# JLinkV9-nano.net
KiCad netlist of a schematic drawn in Altium Designer
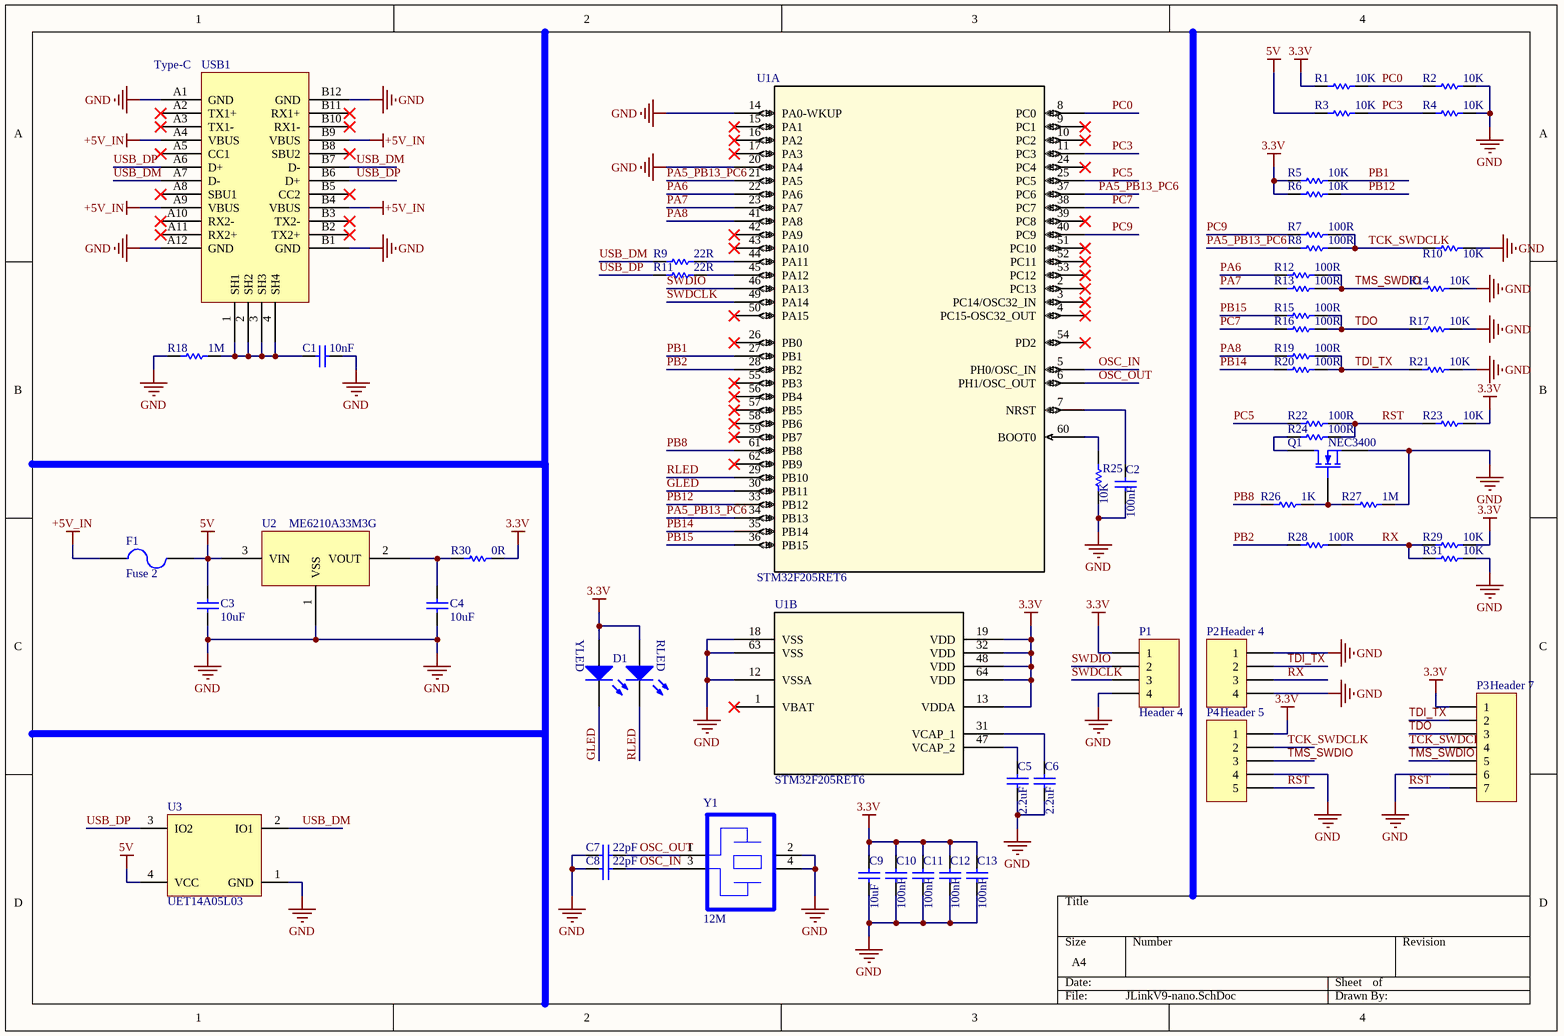
[diagram p0: JLinkV9-nano.SchDoc]

(export (version "E")
  (design (tool "Eeschema 10.0.6"))
  (components
    (comp (ref "C1")
      (value "10nF")
      (footprint "C0402")
      (description "Capacitor")
      (fields (field (name "Comment") "Cap") (field (name "PUBLISHER") "Altium Limited"))
      (libsource (lib "Misc") (part "Cap"))
    )
    (comp (ref "C2")
      (value "100nF")
      (footprint "C0402")
      (description "Capacitor")
      (fields (field (name "Comment") "Cap") (field (name "PUBLISHER") "Altium Limited"))
      (libsource (lib "Misc") (part "Cap"))
    )
    (comp (ref "C3")
      (value "10uF")
      (footprint "C0603")
      (description "Capacitor")
      (fields (field (name "Comment") "Cap") (field (name "PUBLISHER") "Altium Limited"))
      (libsource (lib "Misc") (part "Cap"))
    )
    (comp (ref "C4")
      (value "10uF")
      (footprint "C0603")
      (description "Capacitor")
      (fields (field (name "Comment") "Cap") (field (name "PUBLISHER") "Altium Limited"))
      (libsource (lib "Misc") (part "Cap"))
    )
    (comp (ref "C5")
      (value "2.2uF")
      (footprint "C0402")
      (description "Capacitor")
      (fields (field (name "Comment") "Cap") (field (name "PUBLISHER") "Altium Limited"))
      (libsource (lib "Misc") (part "Cap"))
    )
    (comp (ref "C6")
      (value "2.2uF")
      (footprint "C0402")
      (description "Capacitor")
      (fields (field (name "Comment") "Cap") (field (name "PUBLISHER") "Altium Limited"))
      (libsource (lib "Misc") (part "Cap"))
    )
    (comp (ref "C7")
      (value "22pF")
      (footprint "C0402")
      (description "Capacitor")
      (fields (field (name "Comment") "Cap") (field (name "PUBLISHER") "Altium Limited"))
      (libsource (lib "Misc") (part "Cap"))
    )
    (comp (ref "C8")
      (value "22pF")
      (footprint "C0402")
      (description "Capacitor")
      (fields (field (name "Comment") "Cap") (field (name "PUBLISHER") "Altium Limited"))
      (libsource (lib "Misc") (part "Cap"))
    )
    (comp (ref "C9")
      (value "10uF")
      (footprint "C0603")
      (description "Capacitor")
      (fields (field (name "Comment") "Cap") (field (name "PUBLISHER") "Altium Limited"))
      (libsource (lib "Misc") (part "Cap"))
    )
    (comp (ref "C10")
      (value "100nF")
      (footprint "C0402")
      (description "Capacitor")
      (fields (field (name "Comment") "Cap") (field (name "PUBLISHER") "Altium Limited"))
      (libsource (lib "Misc") (part "Cap"))
    )
    (comp (ref "C11")
      (value "100nF")
      (footprint "C0402")
      (description "Capacitor")
      (fields (field (name "Comment") "Cap") (field (name "PUBLISHER") "Altium Limited"))
      (libsource (lib "Misc") (part "Cap"))
    )
    (comp (ref "C12")
      (value "100nF")
      (footprint "C0402")
      (description "Capacitor")
      (fields (field (name "Comment") "Cap") (field (name "PUBLISHER") "Altium Limited"))
      (libsource (lib "Misc") (part "Cap"))
    )
    (comp (ref "C13")
      (value "100nF")
      (footprint "C0402")
      (description "Capacitor")
      (fields (field (name "Comment") "Cap") (field (name "PUBLISHER") "Altium Limited"))
      (libsource (lib "Misc") (part "Cap"))
    )
    (comp (ref "D1")
      (value "LED2")
      (footprint "LED_2")
      (description "Typical RED, GREEN, YELLOW, AMBER GaAs LED")
      (fields (field (name "PUBLISHER") "Altium Limited"))
      (libsource (lib "Misc") (part "LED2"))
    )
    (comp (ref "F1")
      (value "Fuse 2")
      (footprint "R0603")
      (description "Fuse")
      (fields (field (name "PUBLISHER") "Altium Limited"))
      (libsource (lib "Miscellaneous Devices") (part "Fuse 2"))
    )
    (comp (ref "P1")
      (value "Header 4")
      (footprint "2_0MM_4_HEADER")
      (description "Header, 4-Pin")
      (fields (field (name "PUBLISHER") "Altium Limited"))
      (libsource (lib "") (part "Header 4_1"))
    )
    (comp (ref "P2")
      (value "Header 4")
      (footprint "2_0MM_4_HEADER")
      (description "Header, 4-Pin")
      (fields (field (name "PUBLISHER") "Altium Limited"))
      (libsource (lib "Connector") (part "Header 4"))
    )
    (comp (ref "P3")
      (value "Header 7")
      (footprint "2_0MM_7_HEADER")
      (description "Header, 7-Pin")
      (fields (field (name "PUBLISHER") "Altium Limited"))
      (libsource (lib "Connector") (part "Header 7"))
    )
    (comp (ref "P4")
      (value "Header 5")
      (footprint "2_0MM_5_HEADER")
      (description "Header, 5-Pin")
      (fields (field (name "PUBLISHER") "Altium Limited"))
      (libsource (lib "Connector") (part "Header 5"))
    )
    (comp (ref "Q1")
      (value "NEC3400")
      (footprint "SOT-23_L")
      (description "N-Channel MOSFET")
      (fields (field (name "PUBLISHER") "Altium Limited"))
      (libsource (lib "Miscellaneous Devices") (part "MOSFET-N"))
    )
    (comp (ref "R1")
      (value "10K")
      (footprint "R0402")
      (description "Resistor")
      (fields (field (name "Comment") "Res") (field (name "PUBLISHER") "Altium Limited"))
      (libsource (lib "Misc") (part "Res"))
    )
    (comp (ref "R2")
      (value "10K")
      (footprint "R0402")
      (description "Resistor")
      (fields (field (name "Comment") "Res") (field (name "PUBLISHER") "Altium Limited"))
      (libsource (lib "Misc") (part "Res"))
    )
    (comp (ref "R3")
      (value "10K")
      (footprint "R0402")
      (description "Resistor")
      (fields (field (name "Comment") "Res") (field (name "PUBLISHER") "Altium Limited"))
      (libsource (lib "Misc") (part "Res"))
    )
    (comp (ref "R4")
      (value "10K")
      (footprint "R0402")
      (description "Resistor")
      (fields (field (name "Comment") "Res") (field (name "PUBLISHER") "Altium Limited"))
      (libsource (lib "Misc") (part "Res"))
    )
    (comp (ref "R5")
      (value "10K")
      (footprint "R0402")
      (description "Resistor")
      (fields (field (name "Comment") "Res") (field (name "PUBLISHER") "Altium Limited"))
      (libsource (lib "Misc") (part "Res"))
    )
    (comp (ref "R6")
      (value "10K")
      (footprint "R0402")
      (description "Resistor")
      (fields (field (name "Comment") "Res") (field (name "PUBLISHER") "Altium Limited"))
      (libsource (lib "Misc") (part "Res"))
    )
    (comp (ref "R7")
      (value "100R")
      (footprint "R0402")
      (description "Resistor")
      (fields (field (name "Comment") "Res") (field (name "PUBLISHER") "Altium Limited"))
      (libsource (lib "Misc") (part "Res"))
    )
    (comp (ref "R8")
      (value "100R")
      (footprint "R0402")
      (description "Resistor")
      (fields (field (name "Comment") "Res") (field (name "PUBLISHER") "Altium Limited"))
      (libsource (lib "Misc") (part "Res"))
    )
    (comp (ref "R9")
      (value "22R")
      (footprint "R0402")
      (description "Resistor")
      (fields (field (name "Comment") "Res") (field (name "PUBLISHER") "Altium Limited"))
      (libsource (lib "Misc") (part "Res"))
    )
    (comp (ref "R10")
      (value "10K")
      (footprint "R0402")
      (description "Resistor")
      (fields (field (name "Comment") "Res") (field (name "PUBLISHER") "Altium Limited"))
      (libsource (lib "Misc") (part "Res"))
    )
    (comp (ref "R11")
      (value "22R")
      (footprint "R0402")
      (description "Resistor")
      (fields (field (name "Comment") "Res") (field (name "PUBLISHER") "Altium Limited"))
      (libsource (lib "Misc") (part "Res"))
    )
    (comp (ref "R12")
      (value "100R")
      (footprint "R0402")
      (description "Resistor")
      (fields (field (name "Comment") "Res") (field (name "PUBLISHER") "Altium Limited"))
      (libsource (lib "Misc") (part "Res"))
    )
    (comp (ref "R13")
      (value "100R")
      (footprint "R0402")
      (description "Resistor")
      (fields (field (name "Comment") "Res") (field (name "PUBLISHER") "Altium Limited"))
      (libsource (lib "Misc") (part "Res"))
    )
    (comp (ref "R14")
      (value "10K")
      (footprint "R0402")
      (description "Resistor")
      (fields (field (name "Comment") "Res") (field (name "PUBLISHER") "Altium Limited"))
      (libsource (lib "Misc") (part "Res"))
    )
    (comp (ref "R15")
      (value "100R")
      (footprint "R0402")
      (description "Resistor")
      (fields (field (name "Comment") "Res") (field (name "PUBLISHER") "Altium Limited"))
      (libsource (lib "Misc") (part "Res"))
    )
    (comp (ref "R16")
      (value "100R")
      (footprint "R0402")
      (description "Resistor")
      (fields (field (name "Comment") "Res") (field (name "PUBLISHER") "Altium Limited"))
      (libsource (lib "Misc") (part "Res"))
    )
    (comp (ref "R17")
      (value "10K")
      (footprint "R0402")
      (description "Resistor")
      (fields (field (name "Comment") "Res") (field (name "PUBLISHER") "Altium Limited"))
      (libsource (lib "Misc") (part "Res"))
    )
    (comp (ref "R18")
      (value "1M")
      (footprint "R0402")
      (description "Resistor")
      (fields (field (name "Comment") "Res") (field (name "PUBLISHER") "Altium Limited"))
      (libsource (lib "Misc") (part "Res"))
    )
    (comp (ref "R19")
      (value "100R")
      (footprint "R0402")
      (description "Resistor")
      (fields (field (name "Comment") "Res") (field (name "PUBLISHER") "Altium Limited"))
      (libsource (lib "Misc") (part "Res"))
    )
    (comp (ref "R20")
      (value "100R")
      (footprint "R0402")
      (description "Resistor")
      (fields (field (name "Comment") "Res") (field (name "PUBLISHER") "Altium Limited"))
      (libsource (lib "Misc") (part "Res"))
    )
    (comp (ref "R21")
      (value "10K")
      (footprint "R0402")
      (description "Resistor")
      (fields (field (name "Comment") "Res") (field (name "PUBLISHER") "Altium Limited"))
      (libsource (lib "Misc") (part "Res"))
    )
    (comp (ref "R22")
      (value "100R")
      (footprint "R0402")
      (description "Resistor")
      (fields (field (name "Comment") "Res") (field (name "PUBLISHER") "Altium Limited"))
      (libsource (lib "Misc") (part "Res"))
    )
    (comp (ref "R23")
      (value "10K")
      (footprint "R0402")
      (description "Resistor")
      (fields (field (name "Comment") "Res") (field (name "PUBLISHER") "Altium Limited"))
      (libsource (lib "Misc") (part "Res"))
    )
    (comp (ref "R24")
      (value "100R")
      (footprint "R0402")
      (description "Resistor")
      (fields (field (name "Comment") "Res") (field (name "PUBLISHER") "Altium Limited"))
      (libsource (lib "Misc") (part "Res"))
    )
    (comp (ref "R25")
      (value "10K")
      (footprint "R0402")
      (description "Resistor")
      (fields (field (name "Comment") "Res") (field (name "PUBLISHER") "Altium Limited"))
      (libsource (lib "Misc") (part "Res"))
    )
    (comp (ref "R26")
      (value "1K")
      (footprint "R0402")
      (description "Resistor")
      (fields (field (name "Comment") "Res") (field (name "PUBLISHER") "Altium Limited"))
      (libsource (lib "Misc") (part "Res"))
    )
    (comp (ref "R27")
      (value "1M")
      (footprint "R0402")
      (description "Resistor")
      (fields (field (name "Comment") "Res") (field (name "PUBLISHER") "Altium Limited"))
      (libsource (lib "Misc") (part "Res"))
    )
    (comp (ref "R28")
      (value "100R")
      (footprint "R0402")
      (description "Resistor")
      (fields (field (name "Comment") "Res") (field (name "PUBLISHER") "Altium Limited"))
      (libsource (lib "Misc") (part "Res"))
    )
    (comp (ref "R29")
      (value "10K")
      (footprint "R0402")
      (description "Resistor")
      (fields (field (name "Comment") "Res") (field (name "PUBLISHER") "Altium Limited"))
      (libsource (lib "Misc") (part "Res"))
    )
    (comp (ref "R30")
      (value "0R")
      (footprint "R0402")
      (description "Resistor")
      (fields (field (name "Comment") "Res") (field (name "PUBLISHER") "Altium Limited"))
      (libsource (lib "Misc") (part "Res"))
    )
    (comp (ref "R31")
      (value "10K")
      (footprint "R0402")
      (description "Resistor")
      (fields (field (name "Comment") "Res") (field (name "PUBLISHER") "Altium Limited"))
      (libsource (lib "Misc") (part "Res"))
    )
    (comp (ref "U1")
      (value "STM32F205RET6")
      (footprint "LQFP64-10x10mm")
      (description "No Description Available")
      (fields (field (name "COPYRIGHT") "Copyright (C) 2021 Ultra Librarian. All rights reserved."))
      (libsource (lib "STM32F205RET6") (part "STM32F205RET6"))
    )
    (comp (ref "U2")
      (value "ME6210A33M3G")
      (footprint "SOT-23_L")
      (libsource (lib "ldo") (part "ME6210A33M3G"))
    )
    (comp (ref "U3") (value "UET14A05L03") (footprint "SOT-143_L") (libsource (lib "protect") (part "ESD4")))
    (comp (ref "USB1")
      (value "Type-C")
      (footprint "Connector:USB-Type-C")
      (libsource (lib "Connector") (part "USB-TYPE-C"))
    )
    (comp (ref "Y1") (value "12M") (footprint "XTAL4") (libsource (lib "Private") (part "XTAL4")))
  )
  (nets
    (net (code "1") (name "+5V_IN") (class "Default")
      (node (ref "F1") (pin "1") (pinfunction "1_1") (pintype "passive"))
      (node (ref "USB1") (pin "A4") (pinfunction "VBUS_A4") (pintype "passive"))
      (node (ref "USB1") (pin "A9") (pinfunction "VBUS_A9") (pintype "passive"))
      (node (ref "USB1") (pin "B4") (pinfunction "VBUS_B4") (pintype "passive"))
      (node (ref "USB1") (pin "B9") (pinfunction "VBUS_B9") (pintype "passive"))
    )
    (net (code "2") (name "/GLED") (class "Default")
      (node (ref "D1") (pin "4") (pinfunction "K_4") (pintype "passive"))
      (node (ref "U1") (pin "30") (pinfunction "PB11_30") (pintype "bidirectional"))
    )
    (net (code "3") (name "/OSC_IN") (class "Default")
      (node (ref "C8") (pin "1") (pinfunction "1_1") (pintype "passive"))
      (node (ref "U1") (pin "5") (pinfunction "PH0/OSC_IN_5") (pintype "bidirectional"))
      (node (ref "Y1") (pin "3") (pinfunction "OSC2_3") (pintype "passive"))
    )
    (net (code "4") (name "/OSC_OUT") (class "Default")
      (node (ref "C7") (pin "1") (pinfunction "1_1") (pintype "passive"))
      (node (ref "U1") (pin "6") (pinfunction "PH1/OSC_OUT_6") (pintype "bidirectional"))
      (node (ref "Y1") (pin "1") (pinfunction "OSC1_1") (pintype "passive"))
    )
    (net (code "5") (name "/PA5_PB13_PC6") (class "Default")
      (node (ref "R8") (pin "1") (pinfunction "1_1") (pintype "passive"))
      (node (ref "U1") (pin "21") (pinfunction "PA5_21") (pintype "bidirectional"))
      (node (ref "U1") (pin "34") (pinfunction "PB13_34") (pintype "bidirectional"))
      (node (ref "U1") (pin "37") (pinfunction "PC6_37") (pintype "bidirectional"))
    )
    (net (code "6") (name "/PA6") (class "Default")
      (node (ref "R12") (pin "1") (pinfunction "1_1") (pintype "passive"))
      (node (ref "U1") (pin "22") (pinfunction "PA6_22") (pintype "bidirectional"))
    )
    (net (code "7") (name "/PA7") (class "Default")
      (node (ref "R13") (pin "1") (pinfunction "1_1") (pintype "passive"))
      (node (ref "U1") (pin "23") (pinfunction "PA7_23") (pintype "bidirectional"))
    )
    (net (code "8") (name "/PA8") (class "Default")
      (node (ref "R19") (pin "1") (pinfunction "1_1") (pintype "passive"))
      (node (ref "U1") (pin "41") (pinfunction "PA8_41") (pintype "bidirectional"))
    )
    (net (code "9") (name "/PB1") (class "Default")
      (node (ref "R5") (pin "2") (pinfunction "2_2") (pintype "passive"))
      (node (ref "U1") (pin "27") (pinfunction "PB1_27") (pintype "bidirectional"))
    )
    (net (code "10") (name "/PB2") (class "Default")
      (node (ref "R28") (pin "1") (pinfunction "1_1") (pintype "passive"))
      (node (ref "U1") (pin "28") (pinfunction "PB2_28") (pintype "bidirectional"))
    )
    (net (code "11") (name "/PB8") (class "Default")
      (node (ref "R26") (pin "1") (pinfunction "1_1") (pintype "passive"))
      (node (ref "U1") (pin "61") (pinfunction "PB8_61") (pintype "bidirectional"))
    )
    (net (code "12") (name "/PB12") (class "Default")
      (node (ref "R6") (pin "2") (pinfunction "2_2") (pintype "passive"))
      (node (ref "U1") (pin "33") (pinfunction "PB12_33") (pintype "bidirectional"))
    )
    (net (code "13") (name "/PB14") (class "Default")
      (node (ref "R20") (pin "1") (pinfunction "1_1") (pintype "passive"))
      (node (ref "U1") (pin "35") (pinfunction "PB14_35") (pintype "bidirectional"))
    )
    (net (code "14") (name "/PB15") (class "Default")
      (node (ref "R15") (pin "1") (pinfunction "1_1") (pintype "passive"))
      (node (ref "U1") (pin "36") (pinfunction "PB15_36") (pintype "bidirectional"))
    )
    (net (code "15") (name "/PC0") (class "Default")
      (node (ref "R1") (pin "2") (pinfunction "2_2") (pintype "passive"))
      (node (ref "R2") (pin "1") (pinfunction "1_1") (pintype "passive"))
      (node (ref "U1") (pin "8") (pinfunction "PC0_8") (pintype "bidirectional"))
    )
    (net (code "16") (name "/PC3") (class "Default")
      (node (ref "R3") (pin "2") (pinfunction "2_2") (pintype "passive"))
      (node (ref "R4") (pin "1") (pinfunction "1_1") (pintype "passive"))
      (node (ref "U1") (pin "11") (pinfunction "PC3_11") (pintype "bidirectional"))
    )
    (net (code "17") (name "/PC5") (class "Default")
      (node (ref "R22") (pin "1") (pinfunction "1_1") (pintype "passive"))
      (node (ref "U1") (pin "25") (pinfunction "PC5_25") (pintype "bidirectional"))
    )
    (net (code "18") (name "/PC7") (class "Default")
      (node (ref "R16") (pin "1") (pinfunction "1_1") (pintype "passive"))
      (node (ref "U1") (pin "38") (pinfunction "PC7_38") (pintype "bidirectional"))
    )
    (net (code "19") (name "/PC9") (class "Default")
      (node (ref "R7") (pin "1") (pinfunction "1_1") (pintype "passive"))
      (node (ref "U1") (pin "40") (pinfunction "PC9_40") (pintype "bidirectional"))
    )
    (net (code "20") (name "/RLED") (class "Default")
      (node (ref "D1") (pin "2") (pinfunction "K_2") (pintype "passive"))
      (node (ref "U1") (pin "29") (pinfunction "PB10_29") (pintype "bidirectional"))
    )
    (net (code "21") (name "/RST") (class "Default")
      (node (ref "P3") (pin "7") (pinfunction "7_7") (pintype "passive"))
      (node (ref "P4") (pin "5") (pinfunction "5_5") (pintype "passive"))
      (node (ref "R22") (pin "2") (pinfunction "2_2") (pintype "passive"))
      (node (ref "R23") (pin "1") (pinfunction "1_1") (pintype "passive"))
      (node (ref "R24") (pin "2") (pinfunction "2_2") (pintype "passive"))
    )
    (net (code "22") (name "/RX") (class "Default")
      (node (ref "P2") (pin "3") (pinfunction "3_3") (pintype "passive"))
      (node (ref "R28") (pin "2") (pinfunction "2_2") (pintype "passive"))
      (node (ref "R29") (pin "1") (pinfunction "1_1") (pintype "passive"))
      (node (ref "R31") (pin "1") (pinfunction "1_1") (pintype "passive"))
    )
    (net (code "23") (name "/SWDCLK") (class "Default")
      (node (ref "P1") (pin "3") (pinfunction "3_3") (pintype "passive"))
      (node (ref "U1") (pin "49") (pinfunction "PA14_49") (pintype "bidirectional"))
    )
    (net (code "24") (name "/SWDIO") (class "Default")
      (node (ref "P1") (pin "2") (pinfunction "2_2") (pintype "passive"))
      (node (ref "U1") (pin "46") (pinfunction "PA13_46") (pintype "bidirectional"))
    )
    (net (code "25") (name "/TCK_SWDCLK") (class "Default")
      (node (ref "P3") (pin "4") (pinfunction "4_4") (pintype "passive"))
      (node (ref "P4") (pin "2") (pinfunction "2_2") (pintype "passive"))
      (node (ref "R10") (pin "1") (pinfunction "1_1") (pintype "passive"))
      (node (ref "R7") (pin "2") (pinfunction "2_2") (pintype "passive"))
      (node (ref "R8") (pin "2") (pinfunction "2_2") (pintype "passive"))
    )
    (net (code "26") (name "/TDI_TX") (class "Default")
      (node (ref "P2") (pin "2") (pinfunction "2_2") (pintype "passive"))
      (node (ref "P3") (pin "2") (pinfunction "2_2") (pintype "passive"))
      (node (ref "R19") (pin "2") (pinfunction "2_2") (pintype "passive"))
      (node (ref "R20") (pin "2") (pinfunction "2_2") (pintype "passive"))
      (node (ref "R21") (pin "1") (pinfunction "1_1") (pintype "passive"))
    )
    (net (code "27") (name "/TDO") (class "Default")
      (node (ref "P3") (pin "3") (pinfunction "3_3") (pintype "passive"))
      (node (ref "R15") (pin "2") (pinfunction "2_2") (pintype "passive"))
      (node (ref "R16") (pin "2") (pinfunction "2_2") (pintype "passive"))
      (node (ref "R17") (pin "1") (pinfunction "1_1") (pintype "passive"))
    )
    (net (code "28") (name "/TMS_SWDIO") (class "Default")
      (node (ref "P3") (pin "5") (pinfunction "5_5") (pintype "passive"))
      (node (ref "P4") (pin "3") (pinfunction "3_3") (pintype "passive"))
      (node (ref "R12") (pin "2") (pinfunction "2_2") (pintype "passive"))
      (node (ref "R13") (pin "2") (pinfunction "2_2") (pintype "passive"))
      (node (ref "R14") (pin "1") (pinfunction "1_1") (pintype "passive"))
    )
    (net (code "29") (name "/USB_DM") (class "Default")
      (node (ref "R9") (pin "1") (pinfunction "1_1") (pintype "passive"))
      (node (ref "U3") (pin "2") (pinfunction "IO1_2") (pintype "passive"))
      (node (ref "USB1") (pin "A7") (pinfunction "D-_A7") (pintype "passive"))
      (node (ref "USB1") (pin "B7") (pinfunction "D-_B7") (pintype "passive"))
    )
    (net (code "30") (name "/USB_DP") (class "Default")
      (node (ref "R11") (pin "1") (pinfunction "1_1") (pintype "passive"))
      (node (ref "U3") (pin "3") (pinfunction "IO2_3") (pintype "passive"))
      (node (ref "USB1") (pin "A6") (pinfunction "D+_A6") (pintype "passive"))
      (node (ref "USB1") (pin "B6") (pinfunction "D+_B6") (pintype "passive"))
    )
    (net (code "31") (name "3.3V") (class "Default")
      (node (ref "C10") (pin "2") (pinfunction "2_2") (pintype "passive"))
      (node (ref "C11") (pin "2") (pinfunction "2_2") (pintype "passive"))
      (node (ref "C12") (pin "2") (pinfunction "2_2") (pintype "passive"))
      (node (ref "C13") (pin "2") (pinfunction "2_2") (pintype "passive"))
      (node (ref "C9") (pin "2") (pinfunction "2_2") (pintype "passive"))
      (node (ref "D1") (pin "1") (pinfunction "A_1") (pintype "passive"))
      (node (ref "D1") (pin "3") (pinfunction "A_3") (pintype "passive"))
      (node (ref "P1") (pin "1") (pinfunction "1_1") (pintype "passive"))
      (node (ref "P3") (pin "1") (pinfunction "1_1") (pintype "passive"))
      (node (ref "P4") (pin "1") (pinfunction "1_1") (pintype "passive"))
      (node (ref "R1") (pin "1") (pinfunction "1_1") (pintype "passive"))
      (node (ref "R23") (pin "2") (pinfunction "2_2") (pintype "passive"))
      (node (ref "R29") (pin "2") (pinfunction "2_2") (pintype "passive"))
      (node (ref "R30") (pin "2") (pinfunction "2_2") (pintype "passive"))
      (node (ref "R5") (pin "1") (pinfunction "1_1") (pintype "passive"))
      (node (ref "R6") (pin "1") (pinfunction "1_1") (pintype "passive"))
      (node (ref "U1") (pin "13") (pinfunction "VDDA_13") (pintype "power_in"))
      (node (ref "U1") (pin "19") (pinfunction "VDD_19") (pintype "power_in"))
      (node (ref "U1") (pin "32") (pinfunction "VDD_32") (pintype "power_in"))
      (node (ref "U1") (pin "48") (pinfunction "VDD_48") (pintype "power_in"))
      (node (ref "U1") (pin "64") (pinfunction "VDD_64") (pintype "power_in"))
    )
    (net (code "32") (name "5V") (class "Default")
      (node (ref "C3") (pin "2") (pinfunction "2_2") (pintype "passive"))
      (node (ref "F1") (pin "2") (pinfunction "2_2") (pintype "passive"))
      (node (ref "R3") (pin "1") (pinfunction "1_1") (pintype "passive"))
      (node (ref "U2") (pin "3") (pinfunction "VIN_3") (pintype "passive"))
      (node (ref "U3") (pin "4") (pinfunction "VCC_4") (pintype "passive"))
    )
    (net (code "33") (name "GND") (class "Default")
      (node (ref "C1") (pin "2") (pinfunction "2_2") (pintype "passive"))
      (node (ref "C10") (pin "1") (pinfunction "1_1") (pintype "passive"))
      (node (ref "C11") (pin "1") (pinfunction "1_1") (pintype "passive"))
      (node (ref "C12") (pin "1") (pinfunction "1_1") (pintype "passive"))
      (node (ref "C13") (pin "1") (pinfunction "1_1") (pintype "passive"))
      (node (ref "C2") (pin "1") (pinfunction "1_1") (pintype "passive"))
      (node (ref "C3") (pin "1") (pinfunction "1_1") (pintype "passive"))
      (node (ref "C4") (pin "1") (pinfunction "1_1") (pintype "passive"))
      (node (ref "C5") (pin "1") (pinfunction "1_1") (pintype "passive"))
      (node (ref "C6") (pin "1") (pinfunction "1_1") (pintype "passive"))
      (node (ref "C7") (pin "2") (pinfunction "2_2") (pintype "passive"))
      (node (ref "C8") (pin "2") (pinfunction "2_2") (pintype "passive"))
      (node (ref "C9") (pin "1") (pinfunction "1_1") (pintype "passive"))
      (node (ref "P1") (pin "4") (pinfunction "4_4") (pintype "passive"))
      (node (ref "P2") (pin "1") (pinfunction "1_1") (pintype "passive"))
      (node (ref "P2") (pin "4") (pinfunction "4_4") (pintype "passive"))
      (node (ref "P3") (pin "6") (pinfunction "6_6") (pintype "passive"))
      (node (ref "P4") (pin "4") (pinfunction "4_4") (pintype "passive"))
      (node (ref "Q1") (pin "3") (pinfunction "S_3") (pintype "passive"))
      (node (ref "R10") (pin "2") (pinfunction "2_2") (pintype "passive"))
      (node (ref "R14") (pin "2") (pinfunction "2_2") (pintype "passive"))
      (node (ref "R17") (pin "2") (pinfunction "2_2") (pintype "passive"))
      (node (ref "R18") (pin "1") (pinfunction "1_1") (pintype "passive"))
      (node (ref "R2") (pin "2") (pinfunction "2_2") (pintype "passive"))
      (node (ref "R21") (pin "2") (pinfunction "2_2") (pintype "passive"))
      (node (ref "R25") (pin "1") (pinfunction "1_1") (pintype "passive"))
      (node (ref "R27") (pin "2") (pinfunction "2_2") (pintype "passive"))
      (node (ref "R31") (pin "2") (pinfunction "2_2") (pintype "passive"))
      (node (ref "R4") (pin "2") (pinfunction "2_2") (pintype "passive"))
      (node (ref "U1") (pin "12") (pinfunction "VSSA_12") (pintype "power_in"))
      (node (ref "U1") (pin "14") (pinfunction "PA0-WKUP_14") (pintype "bidirectional"))
      (node (ref "U1") (pin "18") (pinfunction "VSS_18") (pintype "power_in"))
      (node (ref "U1") (pin "20") (pinfunction "PA4_20") (pintype "bidirectional"))
      (node (ref "U1") (pin "63") (pinfunction "VSS_63") (pintype "power_in"))
      (node (ref "U2") (pin "1") (pinfunction "VSS_1") (pintype "passive"))
      (node (ref "U3") (pin "1") (pinfunction "GND_1") (pintype "passive"))
      (node (ref "USB1") (pin "A1") (pinfunction "GND_A1") (pintype "passive"))
      (node (ref "USB1") (pin "A12") (pinfunction "GND_A12") (pintype "passive"))
      (node (ref "USB1") (pin "B1") (pinfunction "GND_B1") (pintype "passive"))
      (node (ref "USB1") (pin "B12") (pinfunction "GND_B12") (pintype "passive"))
      (node (ref "Y1") (pin "2") (pinfunction "GND_2") (pintype "passive"))
      (node (ref "Y1") (pin "4") (pinfunction "GND_4") (pintype "passive"))
    )
    (net (code "34") (name "Net-(Q1-D)") (class "Default")
      (node (ref "Q1") (pin "1") (pinfunction "D_1") (pintype "passive"))
      (node (ref "R24") (pin "1") (pinfunction "1_1") (pintype "passive"))
    )
    (net (code "35") (name "Net-(Q1-G)") (class "Default")
      (node (ref "Q1") (pin "2") (pinfunction "G_2") (pintype "passive"))
      (node (ref "R26") (pin "2") (pinfunction "2_2") (pintype "passive"))
      (node (ref "R27") (pin "1") (pinfunction "1_1") (pintype "passive"))
    )
    (net (code "36") (name "Net-(U1A-BOOT0)") (class "Default")
      (node (ref "R25") (pin "2") (pinfunction "2_2") (pintype "passive"))
      (node (ref "U1") (pin "60") (pinfunction "BOOT0_60") (pintype "input"))
    )
    (net (code "37") (name "Net-(U1A-NRST)") (class "Default")
      (node (ref "C2") (pin "2") (pinfunction "2_2") (pintype "passive"))
      (node (ref "U1") (pin "7") (pinfunction "NRST_7") (pintype "bidirectional"))
    )
    (net (code "38") (name "Net-(U1A-PA11)") (class "Default")
      (node (ref "R9") (pin "2") (pinfunction "2_2") (pintype "passive"))
      (node (ref "U1") (pin "44") (pinfunction "PA11_44") (pintype "bidirectional"))
    )
    (net (code "39") (name "Net-(U1A-PA12)") (class "Default")
      (node (ref "R11") (pin "2") (pinfunction "2_2") (pintype "passive"))
      (node (ref "U1") (pin "45") (pinfunction "PA12_45") (pintype "bidirectional"))
    )
    (net (code "40") (name "Net-(U1B-VCAP_1)") (class "Default")
      (node (ref "C6") (pin "2") (pinfunction "2_2") (pintype "passive"))
      (node (ref "U1") (pin "31") (pinfunction "VCAP_1_31") (pintype "power_in"))
    )
    (net (code "41") (name "Net-(U1B-VCAP_2)") (class "Default")
      (node (ref "C5") (pin "2") (pinfunction "2_2") (pintype "passive"))
      (node (ref "U1") (pin "47") (pinfunction "VCAP_2_47") (pintype "power_in"))
    )
    (net (code "42") (name "Net-(U2-VOUT)") (class "Default")
      (node (ref "C4") (pin "2") (pinfunction "2_2") (pintype "passive"))
      (node (ref "R30") (pin "1") (pinfunction "1_1") (pintype "passive"))
      (node (ref "U2") (pin "2") (pinfunction "VOUT_2") (pintype "passive"))
    )
    (net (code "43") (name "Net-(USB1-SH1)") (class "Default")
      (node (ref "C1") (pin "1") (pinfunction "1_1") (pintype "passive"))
      (node (ref "R18") (pin "2") (pinfunction "2_2") (pintype "passive"))
      (node (ref "USB1") (pin "1") (pinfunction "SH1_1") (pintype "passive"))
      (node (ref "USB1") (pin "2") (pinfunction "SH2_2") (pintype "passive"))
      (node (ref "USB1") (pin "3") (pinfunction "SH3_3") (pintype "passive"))
      (node (ref "USB1") (pin "4") (pinfunction "SH4_4") (pintype "passive"))
    )
    (net (code "44") (name "unconnected-(U1A-PA1-Pad15)") (class "Default")
      (node (ref "U1") (pin "15") (pinfunction "PA1_15") (pintype "bidirectional+no_connect"))
    )
    (net (code "45") (name "unconnected-(U1A-PA2-Pad16)") (class "Default")
      (node (ref "U1") (pin "16") (pinfunction "PA2_16") (pintype "bidirectional+no_connect"))
    )
    (net (code "46") (name "unconnected-(U1A-PA3-Pad17)") (class "Default")
      (node (ref "U1") (pin "17") (pinfunction "PA3_17") (pintype "bidirectional+no_connect"))
    )
    (net (code "47") (name "unconnected-(U1A-PA9-Pad42)") (class "Default")
      (node (ref "U1") (pin "42") (pinfunction "PA9_42") (pintype "bidirectional+no_connect"))
    )
    (net (code "48") (name "unconnected-(U1A-PA10-Pad43)") (class "Default")
      (node (ref "U1") (pin "43") (pinfunction "PA10_43") (pintype "bidirectional+no_connect"))
    )
    (net (code "49") (name "unconnected-(U1A-PA15-Pad50)") (class "Default")
      (node (ref "U1") (pin "50") (pinfunction "PA15_50") (pintype "bidirectional+no_connect"))
    )
    (net (code "50") (name "unconnected-(U1A-PB0-Pad26)") (class "Default")
      (node (ref "U1") (pin "26") (pinfunction "PB0_26") (pintype "bidirectional+no_connect"))
    )
    (net (code "51") (name "unconnected-(U1A-PB3-Pad55)") (class "Default")
      (node (ref "U1") (pin "55") (pinfunction "PB3_55") (pintype "bidirectional+no_connect"))
    )
    (net (code "52") (name "unconnected-(U1A-PB4-Pad56)") (class "Default")
      (node (ref "U1") (pin "56") (pinfunction "PB4_56") (pintype "bidirectional+no_connect"))
    )
    (net (code "53") (name "unconnected-(U1A-PB5-Pad57)") (class "Default")
      (node (ref "U1") (pin "57") (pinfunction "PB5_57") (pintype "bidirectional+no_connect"))
    )
    (net (code "54") (name "unconnected-(U1A-PB6-Pad58)") (class "Default")
      (node (ref "U1") (pin "58") (pinfunction "PB6_58") (pintype "bidirectional+no_connect"))
    )
    (net (code "55") (name "unconnected-(U1A-PB7-Pad59)") (class "Default")
      (node (ref "U1") (pin "59") (pinfunction "PB7_59") (pintype "bidirectional+no_connect"))
    )
    (net (code "56") (name "unconnected-(U1A-PB9-Pad62)") (class "Default")
      (node (ref "U1") (pin "62") (pinfunction "PB9_62") (pintype "bidirectional+no_connect"))
    )
    (net (code "57") (name "unconnected-(U1A-PC1-Pad9)") (class "Default")
      (node (ref "U1") (pin "9") (pinfunction "PC1_9") (pintype "bidirectional+no_connect"))
    )
    (net (code "58") (name "unconnected-(U1A-PC2-Pad10)") (class "Default")
      (node (ref "U1") (pin "10") (pinfunction "PC2_10") (pintype "bidirectional+no_connect"))
    )
    (net (code "59") (name "unconnected-(U1A-PC4-Pad24)") (class "Default")
      (node (ref "U1") (pin "24") (pinfunction "PC4_24") (pintype "bidirectional+no_connect"))
    )
    (net (code "60") (name "unconnected-(U1A-PC8-Pad39)") (class "Default")
      (node (ref "U1") (pin "39") (pinfunction "PC8_39") (pintype "bidirectional+no_connect"))
    )
    (net (code "61") (name "unconnected-(U1A-PC10-Pad51)") (class "Default")
      (node (ref "U1") (pin "51") (pinfunction "PC10_51") (pintype "bidirectional+no_connect"))
    )
    (net (code "62") (name "unconnected-(U1A-PC11-Pad52)") (class "Default")
      (node (ref "U1") (pin "52") (pinfunction "PC11_52") (pintype "bidirectional+no_connect"))
    )
    (net (code "63") (name "unconnected-(U1A-PC12-Pad53)") (class "Default")
      (node (ref "U1") (pin "53") (pinfunction "PC12_53") (pintype "bidirectional+no_connect"))
    )
    (net (code "64") (name "unconnected-(U1A-PC13-Pad2)") (class "Default")
      (node (ref "U1") (pin "2") (pinfunction "PC13_2") (pintype "bidirectional+no_connect"))
    )
    (net (code "65") (name "unconnected-(U1A-PC14{slash}OSC32_IN-Pad3)") (class "Default")
      (node (ref "U1") (pin "3") (pinfunction "PC14/OSC32_IN_3") (pintype "bidirectional+no_connect"))
    )
    (net (code "66") (name "unconnected-(U1A-PC15-OSC32_OUT-Pad4)") (class "Default")
      (node (ref "U1") (pin "4") (pinfunction "PC15-OSC32_OUT_4") (pintype "bidirectional+no_connect"))
    )
    (net (code "67") (name "unconnected-(U1A-PD2-Pad54)") (class "Default")
      (node (ref "U1") (pin "54") (pinfunction "PD2_54") (pintype "bidirectional+no_connect"))
    )
    (net (code "68") (name "unconnected-(U1B-VBAT-Pad1)") (class "Default")
      (node (ref "U1") (pin "1") (pinfunction "VBAT_1") (pintype "power_in+no_connect"))
    )
    (net (code "69") (name "unconnected-(USB1-CC1-PadA5)") (class "Default")
      (node (ref "USB1") (pin "A5") (pinfunction "CC1_A5") (pintype "passive+no_connect"))
    )
    (net (code "70") (name "unconnected-(USB1-CC2-PadB5)") (class "Default")
      (node (ref "USB1") (pin "B5") (pinfunction "CC2_B5") (pintype "passive+no_connect"))
    )
    (net (code "71") (name "unconnected-(USB1-RX1+-PadB11)") (class "Default")
      (node (ref "USB1") (pin "B11") (pinfunction "RX1+_B11") (pintype "passive+no_connect"))
    )
    (net (code "72") (name "unconnected-(USB1-RX1--PadB10)") (class "Default")
      (node (ref "USB1") (pin "B10") (pinfunction "RX1-_B10") (pintype "passive+no_connect"))
    )
    (net (code "73") (name "unconnected-(USB1-RX2+-PadA11)") (class "Default")
      (node (ref "USB1") (pin "A11") (pinfunction "RX2+_A11") (pintype "passive+no_connect"))
    )
    (net (code "74") (name "unconnected-(USB1-RX2--PadA10)") (class "Default")
      (node (ref "USB1") (pin "A10") (pinfunction "RX2-_A10") (pintype "passive+no_connect"))
    )
    (net (code "75") (name "unconnected-(USB1-SBU1-PadA8)") (class "Default")
      (node (ref "USB1") (pin "A8") (pinfunction "SBU1_A8") (pintype "passive+no_connect"))
    )
    (net (code "76") (name "unconnected-(USB1-SBU2-PadB8)") (class "Default")
      (node (ref "USB1") (pin "B8") (pinfunction "SBU2_B8") (pintype "passive+no_connect"))
    )
    (net (code "77") (name "unconnected-(USB1-TX1+-PadA2)") (class "Default")
      (node (ref "USB1") (pin "A2") (pinfunction "TX1+_A2") (pintype "passive+no_connect"))
    )
    (net (code "78") (name "unconnected-(USB1-TX1--PadA3)") (class "Default")
      (node (ref "USB1") (pin "A3") (pinfunction "TX1-_A3") (pintype "passive+no_connect"))
    )
    (net (code "79") (name "unconnected-(USB1-TX2+-PadB2)") (class "Default")
      (node (ref "USB1") (pin "B2") (pinfunction "TX2+_B2") (pintype "passive+no_connect"))
    )
    (net (code "80") (name "unconnected-(USB1-TX2--PadB3)") (class "Default")
      (node (ref "USB1") (pin "B3") (pinfunction "TX2-_B3") (pintype "passive+no_connect"))
    )
  )
)
